# ADCMP.net
KiCad netlist of a schematic drawn in Altium Designer
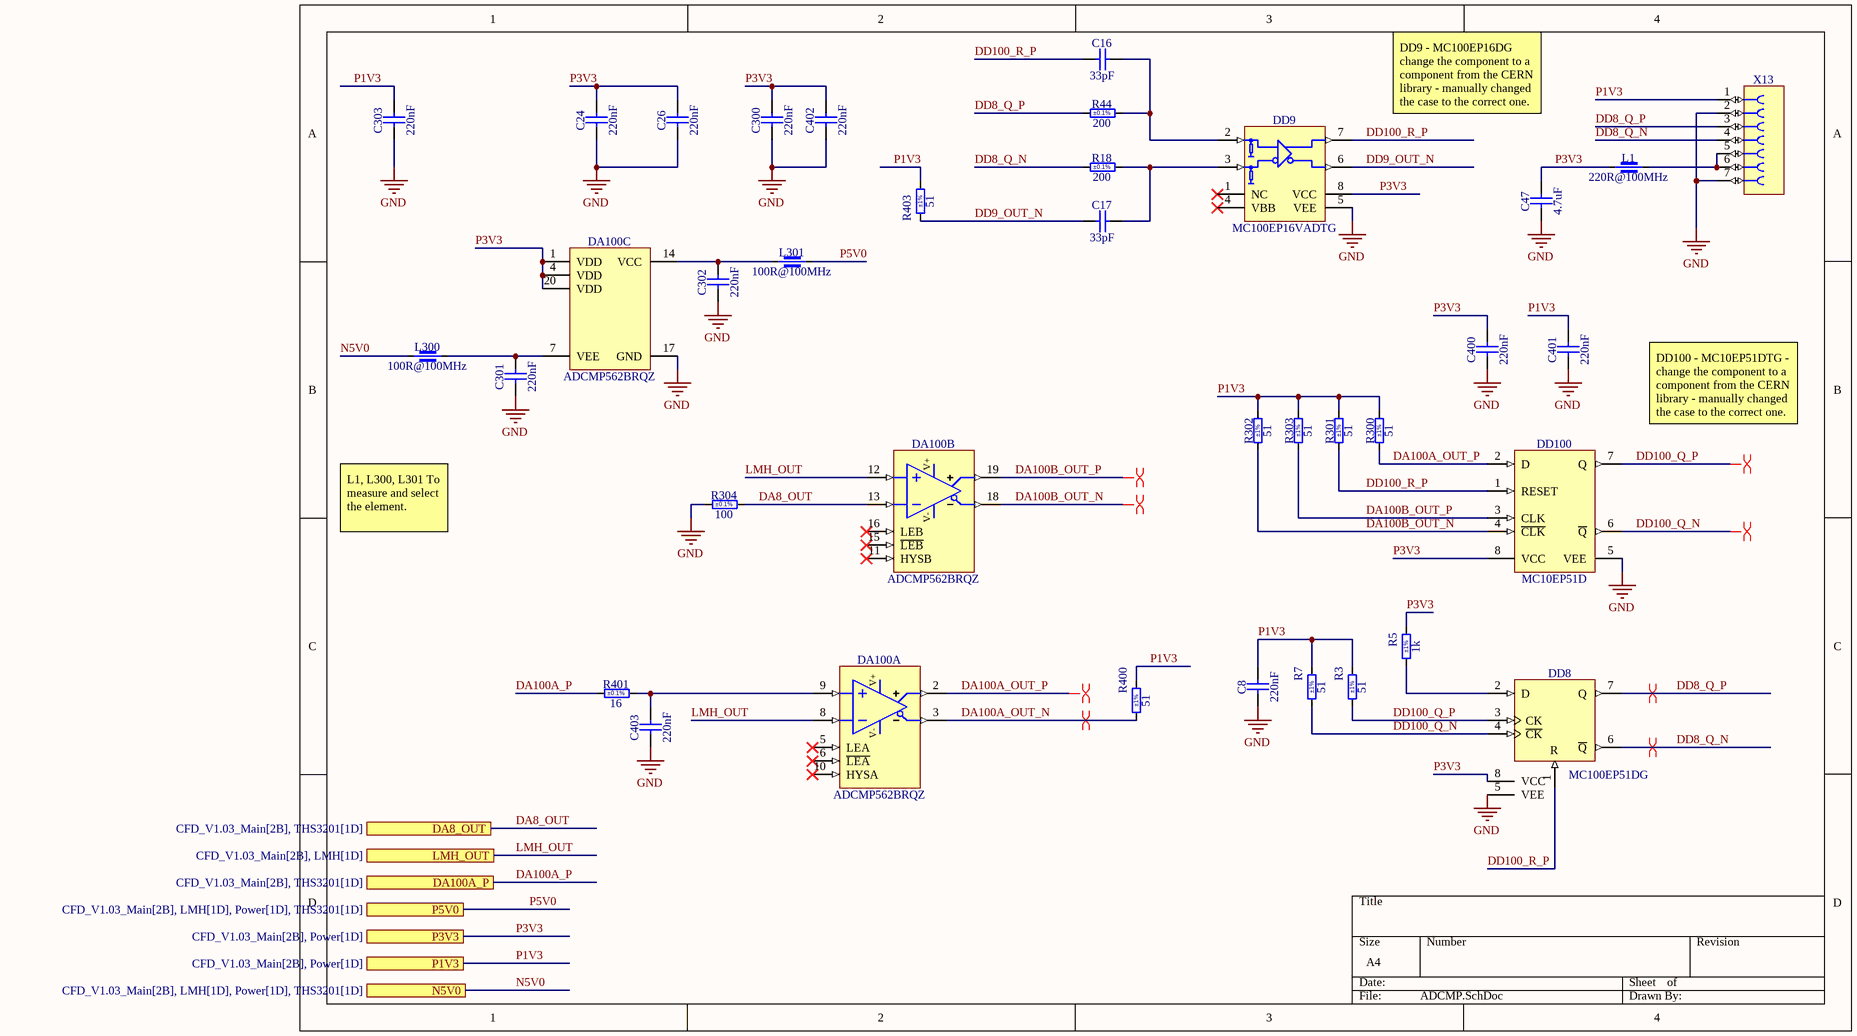
[diagram p0: ADCMP.SchDoc]

(export (version "E")
  (design (tool "Eeschema 10.0.6"))
  (components
    (comp (ref "C8")
      (value "220nF")
      (footprint "CAPC2012X135N")
      (description "Non-polarised capacitor")
      (fields
        (field (name "PART NUMBER") "CC0805_220NF_50V_10%_X7R")
        (field (name "VOLTAGE") "50V")
        (field (name "AUTHOR") "CERN DEM JLC")
      )
      (libsource (lib "Capacitors") (part "Capacitor - non polarized"))
    )
    (comp (ref "C16")
      (value "33pF")
      (footprint "CAPC2012X135N")
      (description "Non-polarised capacitor")
      (fields
        (field (name "PART NUMBER") "CC0805_33PF_50V_5%_NP0")
        (field (name "VOLTAGE") "50V")
        (field (name "AUTHOR") "CERN DEM JLC")
      )
      (libsource (lib "Capacitors") (part "Capacitor - non polarized"))
    )
    (comp (ref "C17")
      (value "33pF")
      (footprint "CAPC2012X135N")
      (description "Non-polarised capacitor")
      (fields
        (field (name "PART NUMBER") "CC0805_33PF_50V_5%_NP0")
        (field (name "VOLTAGE") "50V")
        (field (name "AUTHOR") "CERN DEM JLC")
      )
      (libsource (lib "Capacitors") (part "Capacitor - non polarized"))
    )
    (comp (ref "C24")
      (value "220nF")
      (footprint "CAPC2012X135N")
      (description "Non-polarised capacitor")
      (fields
        (field (name "PART NUMBER") "CC0805_220NF_50V_10%_X7R")
        (field (name "VOLTAGE") "50V")
        (field (name "AUTHOR") "CERN DEM JLC")
      )
      (libsource (lib "Capacitors") (part "Capacitor - non polarized"))
    )
    (comp (ref "C26")
      (value "220nF")
      (footprint "CAPC2012X135N")
      (description "Non-polarised capacitor")
      (fields
        (field (name "PART NUMBER") "CC0805_220NF_50V_10%_X7R")
        (field (name "VOLTAGE") "50V")
        (field (name "AUTHOR") "CERN DEM JLC")
      )
      (libsource (lib "Capacitors") (part "Capacitor - non polarized"))
    )
    (comp (ref "C47")
      (value "4.7uF")
      (footprint "CAPC3216X180N")
      (description "Non-polarised capacitor")
      (fields
        (field (name "PART NUMBER") "CC1206_4.7UF_25V_10%_X7R")
        (field (name "VOLTAGE") "25V")
        (field (name "AUTHOR") "CERN DEM WB")
      )
      (libsource (lib "Capacitors") (part "Capacitor - non polarized"))
    )
    (comp (ref "C300")
      (value "220nF")
      (footprint "CAPC1608X87N")
      (description "Non-polarised capacitor")
      (fields
        (field (name "PART NUMBER") "CC0603_220NF_25V_10%_X7R")
        (field (name "VOLTAGE") "25V")
        (field (name "AUTHOR") "CERN DEM JLC")
      )
      (libsource (lib "Capacitors") (part "Capacitor - non polarized"))
    )
    (comp (ref "C301")
      (value "220nF")
      (footprint "CAPC1608X87N")
      (description "Non-polarised capacitor")
      (fields
        (field (name "PART NUMBER") "CC0603_220NF_25V_10%_X7R")
        (field (name "VOLTAGE") "25V")
        (field (name "AUTHOR") "CERN DEM JLC")
      )
      (libsource (lib "Capacitors") (part "Capacitor - non polarized"))
    )
    (comp (ref "C302")
      (value "220nF")
      (footprint "CAPC1608X87N")
      (description "Non-polarised capacitor")
      (fields
        (field (name "PART NUMBER") "CC0603_220NF_25V_10%_X7R")
        (field (name "VOLTAGE") "25V")
        (field (name "AUTHOR") "CERN DEM JLC")
      )
      (libsource (lib "Capacitors") (part "Capacitor - non polarized"))
    )
    (comp (ref "C303")
      (value "220nF")
      (footprint "CAPC2012X135N")
      (description "Non-polarised capacitor")
      (fields
        (field (name "PART NUMBER") "CC0805_220NF_50V_10%_X7R")
        (field (name "VOLTAGE") "50V")
        (field (name "AUTHOR") "CERN DEM JLC")
      )
      (libsource (lib "Capacitors") (part "Capacitor - non polarized"))
    )
    (comp (ref "C400")
      (value "220nF")
      (footprint "CAPC2012X135N")
      (description "Non-polarised capacitor")
      (fields
        (field (name "PART NUMBER") "CC0805_220NF_50V_10%_X7R")
        (field (name "VOLTAGE") "50V")
        (field (name "AUTHOR") "CERN DEM JLC")
      )
      (libsource (lib "Capacitors") (part "Capacitor - non polarized"))
    )
    (comp (ref "C401")
      (value "220nF")
      (footprint "CAPC2012X135N")
      (description "Non-polarised capacitor")
      (fields
        (field (name "PART NUMBER") "CC0805_220NF_50V_10%_X7R")
        (field (name "VOLTAGE") "50V")
        (field (name "AUTHOR") "CERN DEM JLC")
      )
      (libsource (lib "Capacitors") (part "Capacitor - non polarized"))
    )
    (comp (ref "C402")
      (value "220nF")
      (footprint "CAPC1608X87N")
      (description "Non-polarised capacitor")
      (fields
        (field (name "PART NUMBER") "CC0603_220NF_25V_10%_X7R")
        (field (name "VOLTAGE") "25V")
        (field (name "AUTHOR") "CERN DEM JLC")
      )
      (libsource (lib "Capacitors") (part "Capacitor - non polarized"))
    )
    (comp (ref "C403")
      (value "220nF")
      (footprint "CAPC1608X87N")
      (description "Non-polarised capacitor")
      (fields
        (field (name "PART NUMBER") "CC0603_220NF_25V_10%_X7R")
        (field (name "VOLTAGE") "25V")
        (field (name "AUTHOR") "CERN DEM JLC")
      )
      (libsource (lib "Capacitors") (part "Capacitor - non polarized"))
    )
    (comp (ref "DA100")
      (value "ADCMP562BRQZ")
      (footprint "SOP63P600X175-20AN")
      (description "Dual, High Speed PECL Comparators")
      (fields
        (field (name "MANUFACTURER") "ANALOG DEVICES")
        (field (name "MANUFACTURER PART NUMBER") "ADCMP562BRQ")
        (field (name "AUTHOR") "CERN DEM MR")
      )
      (libsource (lib "ICs And Semiconductors") (part "ADCMP562BRQZ"))
    )
    (comp (ref "DD8")
      (value "MC100EP51DG")
      (footprint "SOIC127P600X175-8N")
      (description "3.3V/5V ECL D Flip-Flop with Reset and Differential Clock")
      (fields
        (field (name "MANUFACTURER") "ON SEMICONDUCTOR")
        (field (name "MANUFACTURER PART NUMBER") "MC100EP51D")
        (field (name "AUTHOR") "CERN DEM JLC")
      )
      (libsource (lib "ICs And Semiconductors") (part "100EP51"))
    )
    (comp (ref "DD9")
      (value "MC100EP16VADTG")
      (footprint "SOIC127P600X175-8N")
      (description "3.3V / 5V ECL Differential Receiver/Driver with High Gain")
      (fields
        (field (name "MANUFACTURER") "ON SEMICONDUCTOR")
        (field (name "MANUFACTURER PART NUMBER") "MC100EP16VADT")
        (field (name "AUTHOR") "CERN DEM JLC")
      )
      (libsource (lib "ICs And Semiconductors") (part "100EP16"))
    )
    (comp (ref "DD100")
      (value "MC10EP51D")
      (footprint "SOP65P490X110-8N")
      (description "3.3V/5V ECL D Flip-Flop with Reset and Differential Clock")
      (fields (field (name "MANUFACTURER") "ON SEMICONDUCTOR") (field (name "AUTHOR") "CERN DEM HF"))
      (libsource (lib "ICs And Semiconductors") (part "10EP51"))
    )
    (comp (ref "L1")
      (value "220R@100MHz")
      (footprint "INDC2012X105N")
      (fields
        (field (name "PART NUMBER") "IND0805_TDK_MPZ2012S221A")
        (field (name "POWER") "3A")
        (field (name "TOLERANCE") "±25%")
        (field (name "AUTHOR") "CERN DEM HF")
      )
      (libsource (lib "Inductors & Transformers") (part "Ferrite Bead"))
    )
    (comp (ref "L300")
      (value "100R@100MHz")
      (footprint "INDC1608X75N")
      (fields
        (field (name "PART NUMBER") "IND0603_TDK_MPZ1608S101ATAH0")
        (field (name "POWER") "3A")
        (field (name "TOLERANCE") "±25%")
        (field (name "AUTHOR") "CERN DEM JMW")
      )
      (libsource (lib "Inductors & Transformers") (part "Ferrite Bead"))
    )
    (comp (ref "L301")
      (value "100R@100MHz")
      (footprint "INDC1608X75N")
      (fields
        (field (name "PART NUMBER") "IND0603_TDK_MPZ1608S101ATAH0")
        (field (name "POWER") "3A")
        (field (name "TOLERANCE") "±25%")
        (field (name "AUTHOR") "CERN DEM JMW")
      )
      (libsource (lib "Inductors & Transformers") (part "Ferrite Bead"))
    )
    (comp (ref "R3")
      (value "51")
      (footprint "RESC2012X60N")
      (description "Resistor - 1%")
      (fields
        (field (name "TOLERANCE") "±1%")
        (field (name "PART NUMBER") "R0805_51R_1%_0.125W_100PPM")
        (field (name "POWER") "0.125W")
        (field (name "AUTHOR") "CERN DEM JLC")
      )
      (libsource (lib "Resistors") (part "Resistor - 1%"))
    )
    (comp (ref "R5")
      (value "1k")
      (footprint "RESC2012X60N")
      (description "Resistor - 1%")
      (fields
        (field (name "TOLERANCE") "±1%")
        (field (name "PART NUMBER") "R0805_1K_1%_0.125W_100PPM")
        (field (name "POWER") "0.125W")
        (field (name "AUTHOR") "CERN DEM JLC")
      )
      (libsource (lib "Resistors") (part "Resistor - 1%"))
    )
    (comp (ref "R7")
      (value "51")
      (footprint "RESC2012X60N")
      (description "Resistor - 1%")
      (fields
        (field (name "TOLERANCE") "±1%")
        (field (name "PART NUMBER") "R0805_51R_1%_0.125W_100PPM")
        (field (name "POWER") "0.125W")
        (field (name "AUTHOR") "CERN DEM JLC")
      )
      (libsource (lib "Resistors") (part "Resistor - 1%"))
    )
    (comp (ref "R18")
      (value "200")
      (footprint "RESC2012X60N")
      (description "Resistor - 0.1%")
      (fields
        (field (name "TOLERANCE") "±0.1%")
        (field (name "PART NUMBER") "R0805_200R_0.1%_0.1W_10PPM")
        (field (name "POWER") "0.1W")
        (field (name "AUTHOR") "CERN DEM JLC")
      )
      (libsource (lib "Resistors") (part "Resistor - 0.1%"))
    )
    (comp (ref "R44")
      (value "200")
      (footprint "RESC2012X60N")
      (description "Resistor - 0.1%")
      (fields
        (field (name "TOLERANCE") "±0.1%")
        (field (name "PART NUMBER") "R0805_200R_0.1%_0.1W_10PPM")
        (field (name "POWER") "0.1W")
        (field (name "AUTHOR") "CERN DEM JLC")
      )
      (libsource (lib "Resistors") (part "Resistor - 0.1%"))
    )
    (comp (ref "R300")
      (value "51")
      (footprint "RESC2012X60N")
      (description "Resistor - 1%")
      (fields
        (field (name "TOLERANCE") "±1%")
        (field (name "PART NUMBER") "R0805_51R_1%_0.125W_100PPM")
        (field (name "POWER") "0.125W")
        (field (name "AUTHOR") "CERN DEM JLC")
      )
      (libsource (lib "Resistors") (part "Resistor - 1%"))
    )
    (comp (ref "R301")
      (value "51")
      (footprint "RESC2012X60N")
      (description "Resistor - 1%")
      (fields
        (field (name "TOLERANCE") "±1%")
        (field (name "PART NUMBER") "R0805_51R_1%_0.125W_100PPM")
        (field (name "POWER") "0.125W")
        (field (name "AUTHOR") "CERN DEM JLC")
      )
      (libsource (lib "Resistors") (part "Resistor - 1%"))
    )
    (comp (ref "R302")
      (value "51")
      (footprint "RESC2012X60N")
      (description "Resistor - 1%")
      (fields
        (field (name "TOLERANCE") "±1%")
        (field (name "PART NUMBER") "R0805_51R_1%_0.125W_100PPM")
        (field (name "POWER") "0.125W")
        (field (name "AUTHOR") "CERN DEM JLC")
      )
      (libsource (lib "Resistors") (part "Resistor - 1%"))
    )
    (comp (ref "R303")
      (value "51")
      (footprint "RESC2012X60N")
      (description "Resistor - 1%")
      (fields
        (field (name "TOLERANCE") "±1%")
        (field (name "PART NUMBER") "R0805_51R_1%_0.125W_100PPM")
        (field (name "POWER") "0.125W")
        (field (name "AUTHOR") "CERN DEM JLC")
      )
      (libsource (lib "Resistors") (part "Resistor - 1%"))
    )
    (comp (ref "R304")
      (value "100")
      (footprint "RESC1608X55N")
      (description "Resistor - 0.1%")
      (fields
        (field (name "TOLERANCE") "±0.1%")
        (field (name "PART NUMBER") "R0603_100R_0.1%_0.1W_10PPM_VISHAY_MCT")
        (field (name "POWER") "0.1W")
        (field (name "AUTHOR") "CERN DEM BC")
      )
      (libsource (lib "Resistors") (part "Resistor - 0.1%"))
    )
    (comp (ref "R400")
      (value "51")
      (footprint "RESC2012X60N")
      (description "Resistor - 1%")
      (fields
        (field (name "TOLERANCE") "±1%")
        (field (name "PART NUMBER") "R0805_51R_1%_0.125W_100PPM")
        (field (name "POWER") "0.125W")
        (field (name "AUTHOR") "CERN DEM JLC")
      )
      (libsource (lib "Resistors") (part "Resistor - 1%"))
    )
    (comp (ref "R401")
      (value "16")
      (footprint "RESC1608X64N")
      (description "Resistor - 0.1%")
      (fields
        (field (name "TOLERANCE") "±0.1%")
        (field (name "PART NUMBER") "R0603_16R_0.1%_0.1W_10PPM")
        (field (name "POWER") "0.1W")
        (field (name "AUTHOR") "CERN DEM HF")
      )
      (libsource (lib "Resistors") (part "Resistor - 0.1%"))
    )
    (comp (ref "R403")
      (value "51")
      (footprint "RESC2012X60N")
      (description "Resistor - 1%")
      (fields
        (field (name "TOLERANCE") "±1%")
        (field (name "PART NUMBER") "R0805_51R_1%_0.125W_100PPM")
        (field (name "POWER") "0.125W")
        (field (name "AUTHOR") "CERN DEM JLC")
      )
      (libsource (lib "Resistors") (part "Resistor - 1%"))
    )
    (comp (ref "X13")
      (value "Socket 7")
      (footprint "SAMTEC_CES-107-01-T-S")
      (description "Connector 7 Female")
      (fields
        (field (name "PART NUMBER") "SAMTEC_CES-107-01-L-S")
        (field (name "MANUFACTURER") "SAMTEC")
        (field (name "AUTHOR") "CERN DEM HF")
      )
      (libsource (lib "Connectors") (part "Connector 7 Female"))
    )
  )
  (nets
    (net (code "1") (name "/DA8_OUT") (class "Default")
      (node (ref "DA100") (pin "13") (pinfunction "-INB_13") (pintype "input"))
      (node (ref "R304") (pin "2") (pinfunction "2_2") (pintype "passive"))
    )
    (net (code "2") (name "/DA100A_OUT_N") (class "Default")
      (node (ref "DA100") (pin "3") (pinfunction "~{QA}_3") (pintype "output"))
      (node (ref "R400") (pin "1") (pinfunction "1_1") (pintype "passive"))
    )
    (net (code "3") (name "/DA100A_OUT_P") (class "Default")
      (node (ref "DA100") (pin "2") (pinfunction "QA_2") (pintype "output"))
      (node (ref "DD100") (pin "2") (pinfunction "D_2") (pintype "input"))
      (node (ref "R300") (pin "1") (pinfunction "1_1") (pintype "passive"))
    )
    (net (code "4") (name "/DA100A_P") (class "Default")
      (node (ref "R401") (pin "1") (pinfunction "1_1") (pintype "passive"))
    )
    (net (code "5") (name "/DA100B_OUT_N") (class "Default")
      (node (ref "DA100") (pin "18") (pinfunction "~{QB}_18") (pintype "output"))
      (node (ref "DD100") (pin "4") (pinfunction "~{CLK}_4") (pintype "input"))
      (node (ref "R302") (pin "1") (pinfunction "1_1") (pintype "passive"))
    )
    (net (code "6") (name "/DA100B_OUT_P") (class "Default")
      (node (ref "DA100") (pin "19") (pinfunction "QB_19") (pintype "output"))
      (node (ref "DD100") (pin "3") (pinfunction "CLK_3") (pintype "input"))
      (node (ref "R303") (pin "1") (pinfunction "1_1") (pintype "passive"))
    )
    (net (code "7") (name "/DD8_Q_N") (class "Default")
      (node (ref "DD8") (pin "6") (pinfunction "~{Q}_6") (pintype "output"))
      (node (ref "R18") (pin "1") (pinfunction "1_1") (pintype "passive"))
      (node (ref "X13") (pin "4") (pinfunction "4_4") (pintype "bidirectional"))
    )
    (net (code "8") (name "/DD8_Q_P") (class "Default")
      (node (ref "DD8") (pin "7") (pinfunction "Q_7") (pintype "output"))
      (node (ref "R44") (pin "1") (pinfunction "1_1") (pintype "passive"))
      (node (ref "X13") (pin "3") (pinfunction "3_3") (pintype "bidirectional"))
    )
    (net (code "9") (name "/DD9_OUT_N") (class "Default")
      (node (ref "C17") (pin "1") (pinfunction "1_1") (pintype "passive"))
      (node (ref "DD9") (pin "6") (pinfunction "~{Q}_6") (pintype "output"))
      (node (ref "R403") (pin "1") (pinfunction "1_1") (pintype "passive"))
    )
    (net (code "10") (name "/DD100_Q_N") (class "Default")
      (node (ref "DD100") (pin "6") (pinfunction "~{Q}_6") (pintype "output"))
      (node (ref "DD8") (pin "4") (pinfunction "~{CK}_4") (pintype "input"))
      (node (ref "R7") (pin "1") (pinfunction "1_1") (pintype "passive"))
    )
    (net (code "11") (name "/DD100_Q_P") (class "Default")
      (node (ref "DD100") (pin "7") (pinfunction "Q_7") (pintype "output"))
      (node (ref "DD8") (pin "3") (pinfunction "CK_3") (pintype "input"))
      (node (ref "R3") (pin "1") (pinfunction "1_1") (pintype "passive"))
    )
    (net (code "12") (name "/DD100_R_P") (class "Default")
      (node (ref "C16") (pin "1") (pinfunction "1_1") (pintype "passive"))
      (node (ref "DD100") (pin "1") (pinfunction "RESET_1") (pintype "input"))
      (node (ref "DD8") (pin "1") (pinfunction "R_1") (pintype "input"))
      (node (ref "DD9") (pin "7") (pinfunction "Q_7") (pintype "output"))
      (node (ref "R301") (pin "1") (pinfunction "1_1") (pintype "passive"))
    )
    (net (code "13") (name "/LMH_OUT") (class "Default")
      (node (ref "DA100") (pin "12") (pinfunction "+INB_12") (pintype "input"))
      (node (ref "DA100") (pin "8") (pinfunction "-INA_8") (pintype "input"))
    )
    (net (code "14") (name "/N5V0") (class "Default")
      (node (ref "L300") (pin "1") (pinfunction "1_1") (pintype "passive"))
    )
    (net (code "15") (name "/P1V3") (class "Default")
      (node (ref "C303") (pin "2") (pinfunction "2_2") (pintype "passive"))
      (node (ref "C401") (pin "2") (pinfunction "2_2") (pintype "passive"))
      (node (ref "C8") (pin "2") (pinfunction "2_2") (pintype "passive"))
      (node (ref "R3") (pin "2") (pinfunction "2_2") (pintype "passive"))
      (node (ref "R300") (pin "2") (pinfunction "2_2") (pintype "passive"))
      (node (ref "R301") (pin "2") (pinfunction "2_2") (pintype "passive"))
      (node (ref "R302") (pin "2") (pinfunction "2_2") (pintype "passive"))
      (node (ref "R303") (pin "2") (pinfunction "2_2") (pintype "passive"))
      (node (ref "R400") (pin "2") (pinfunction "2_2") (pintype "passive"))
      (node (ref "R403") (pin "2") (pinfunction "2_2") (pintype "passive"))
      (node (ref "R7") (pin "2") (pinfunction "2_2") (pintype "passive"))
      (node (ref "X13") (pin "1") (pinfunction "1_1") (pintype "bidirectional"))
    )
    (net (code "16") (name "/P3V3") (class "Default")
      (node (ref "C24") (pin "2") (pinfunction "2_2") (pintype "passive"))
      (node (ref "C26") (pin "2") (pinfunction "2_2") (pintype "passive"))
      (node (ref "C300") (pin "2") (pinfunction "2_2") (pintype "passive"))
      (node (ref "C400") (pin "2") (pinfunction "2_2") (pintype "passive"))
      (node (ref "C402") (pin "2") (pinfunction "2_2") (pintype "passive"))
      (node (ref "C47") (pin "2") (pinfunction "2_2") (pintype "passive"))
      (node (ref "DA100") (pin "1") (pinfunction "VDD_1") (pintype "power_in"))
      (node (ref "DA100") (pin "20") (pinfunction "VDD_20") (pintype "power_in"))
      (node (ref "DA100") (pin "4") (pinfunction "VDD_4") (pintype "power_in"))
      (node (ref "DD100") (pin "8") (pinfunction "VCC_8") (pintype "power_in"))
      (node (ref "DD8") (pin "8") (pinfunction "VCC_8") (pintype "power_in"))
      (node (ref "DD9") (pin "8") (pinfunction "VCC_8") (pintype "power_in"))
      (node (ref "L1") (pin "1") (pinfunction "1_1") (pintype "passive"))
      (node (ref "R5") (pin "2") (pinfunction "2_2") (pintype "passive"))
    )
    (net (code "17") (name "/P5V0") (class "Default")
      (node (ref "L301") (pin "2") (pinfunction "2_2") (pintype "passive"))
    )
    (net (code "18") (name "GND") (class "Default")
      (node (ref "C24") (pin "1") (pinfunction "1_1") (pintype "passive"))
      (node (ref "C26") (pin "1") (pinfunction "1_1") (pintype "passive"))
      (node (ref "C300") (pin "1") (pinfunction "1_1") (pintype "passive"))
      (node (ref "C301") (pin "1") (pinfunction "1_1") (pintype "passive"))
      (node (ref "C302") (pin "1") (pinfunction "1_1") (pintype "passive"))
      (node (ref "C303") (pin "1") (pinfunction "1_1") (pintype "passive"))
      (node (ref "C400") (pin "1") (pinfunction "1_1") (pintype "passive"))
      (node (ref "C401") (pin "1") (pinfunction "1_1") (pintype "passive"))
      (node (ref "C402") (pin "1") (pinfunction "1_1") (pintype "passive"))
      (node (ref "C403") (pin "1") (pinfunction "1_1") (pintype "passive"))
      (node (ref "C47") (pin "1") (pinfunction "1_1") (pintype "passive"))
      (node (ref "C8") (pin "1") (pinfunction "1_1") (pintype "passive"))
      (node (ref "DA100") (pin "17") (pinfunction "GND_17") (pintype "power_in"))
      (node (ref "DD100") (pin "5") (pinfunction "VEE_5") (pintype "power_in"))
      (node (ref "DD8") (pin "5") (pinfunction "VEE_5") (pintype "power_in"))
      (node (ref "DD9") (pin "5") (pinfunction "VEE_5") (pintype "power_in"))
      (node (ref "R304") (pin "1") (pinfunction "1_1") (pintype "passive"))
      (node (ref "X13") (pin "2") (pinfunction "2_2") (pintype "bidirectional"))
      (node (ref "X13") (pin "7") (pinfunction "7_7") (pintype "bidirectional"))
    )
    (net (code "19") (name "Net-(DA100A-+INA)") (class "Default")
      (node (ref "C403") (pin "2") (pinfunction "2_2") (pintype "passive"))
      (node (ref "DA100") (pin "9") (pinfunction "+INA_9") (pintype "input"))
      (node (ref "R401") (pin "2") (pinfunction "2_2") (pintype "passive"))
    )
    (net (code "20") (name "Net-(DA100C-VCC)") (class "Default")
      (node (ref "C302") (pin "2") (pinfunction "2_2") (pintype "passive"))
      (node (ref "DA100") (pin "14") (pinfunction "VCC_14") (pintype "power_in"))
      (node (ref "L301") (pin "1") (pinfunction "1_1") (pintype "passive"))
    )
    (net (code "21") (name "Net-(DA100C-VEE)") (class "Default")
      (node (ref "C301") (pin "2") (pinfunction "2_2") (pintype "passive"))
      (node (ref "DA100") (pin "7") (pinfunction "VEE_7") (pintype "power_in"))
      (node (ref "L300") (pin "2") (pinfunction "2_2") (pintype "passive"))
    )
    (net (code "22") (name "Net-(DD8-D)") (class "Default")
      (node (ref "DD8") (pin "2") (pinfunction "D_2") (pintype "input"))
      (node (ref "R5") (pin "1") (pinfunction "1_1") (pintype "passive"))
    )
    (net (code "23") (name "Net-(DD9-D0)") (class "Default")
      (node (ref "C16") (pin "2") (pinfunction "2_2") (pintype "passive"))
      (node (ref "DD9") (pin "2") (pinfunction "D0_2") (pintype "input"))
      (node (ref "R44") (pin "2") (pinfunction "2_2") (pintype "passive"))
    )
    (net (code "24") (name "Net-(DD9-~{D0})") (class "Default")
      (node (ref "C17") (pin "2") (pinfunction "2_2") (pintype "passive"))
      (node (ref "DD9") (pin "3") (pinfunction "~{D0}_3") (pintype "input"))
      (node (ref "R18") (pin "2") (pinfunction "2_2") (pintype "passive"))
    )
    (net (code "25") (name "Net-(L1-Pad2)") (class "Default")
      (node (ref "L1") (pin "2") (pinfunction "2_2") (pintype "passive"))
      (node (ref "X13") (pin "5") (pinfunction "5_5") (pintype "bidirectional"))
      (node (ref "X13") (pin "6") (pinfunction "6_6") (pintype "bidirectional"))
    )
    (net (code "26") (name "unconnected-(DA100A-HYSA-Pad10)") (class "Default")
      (node (ref "DA100") (pin "10") (pinfunction "HYSA_10") (pintype "input+no_connect"))
    )
    (net (code "27") (name "unconnected-(DA100A-LEA-Pad5)") (class "Default")
      (node (ref "DA100") (pin "5") (pinfunction "LEA_5") (pintype "input+no_connect"))
    )
    (net (code "28") (name "unconnected-(DA100A-~{LEA}-Pad6)") (class "Default")
      (node (ref "DA100") (pin "6") (pinfunction "~{LEA}_6") (pintype "input+no_connect"))
    )
    (net (code "29") (name "unconnected-(DA100B-HYSB-Pad11)") (class "Default")
      (node (ref "DA100") (pin "11") (pinfunction "HYSB_11") (pintype "input+no_connect"))
    )
    (net (code "30") (name "unconnected-(DA100B-LEB-Pad16)") (class "Default")
      (node (ref "DA100") (pin "16") (pinfunction "LEB_16") (pintype "input+no_connect"))
    )
    (net (code "31") (name "unconnected-(DA100B-~{LEB}-Pad15)") (class "Default")
      (node (ref "DA100") (pin "15") (pinfunction "~{LEB}_15") (pintype "input+no_connect"))
    )
    (net (code "32") (name "unconnected-(DD9-NC-Pad1)") (class "Default")
      (node (ref "DD9") (pin "1") (pinfunction "NC_1") (pintype "passive+no_connect"))
    )
    (net (code "33") (name "unconnected-(DD9-VBB-Pad4)") (class "Default")
      (node (ref "DD9") (pin "4") (pinfunction "VBB_4") (pintype "power_in+no_connect"))
    )
  )
)
